# IHM.net
KiCad netlist of a schematic drawn in Altium Designer
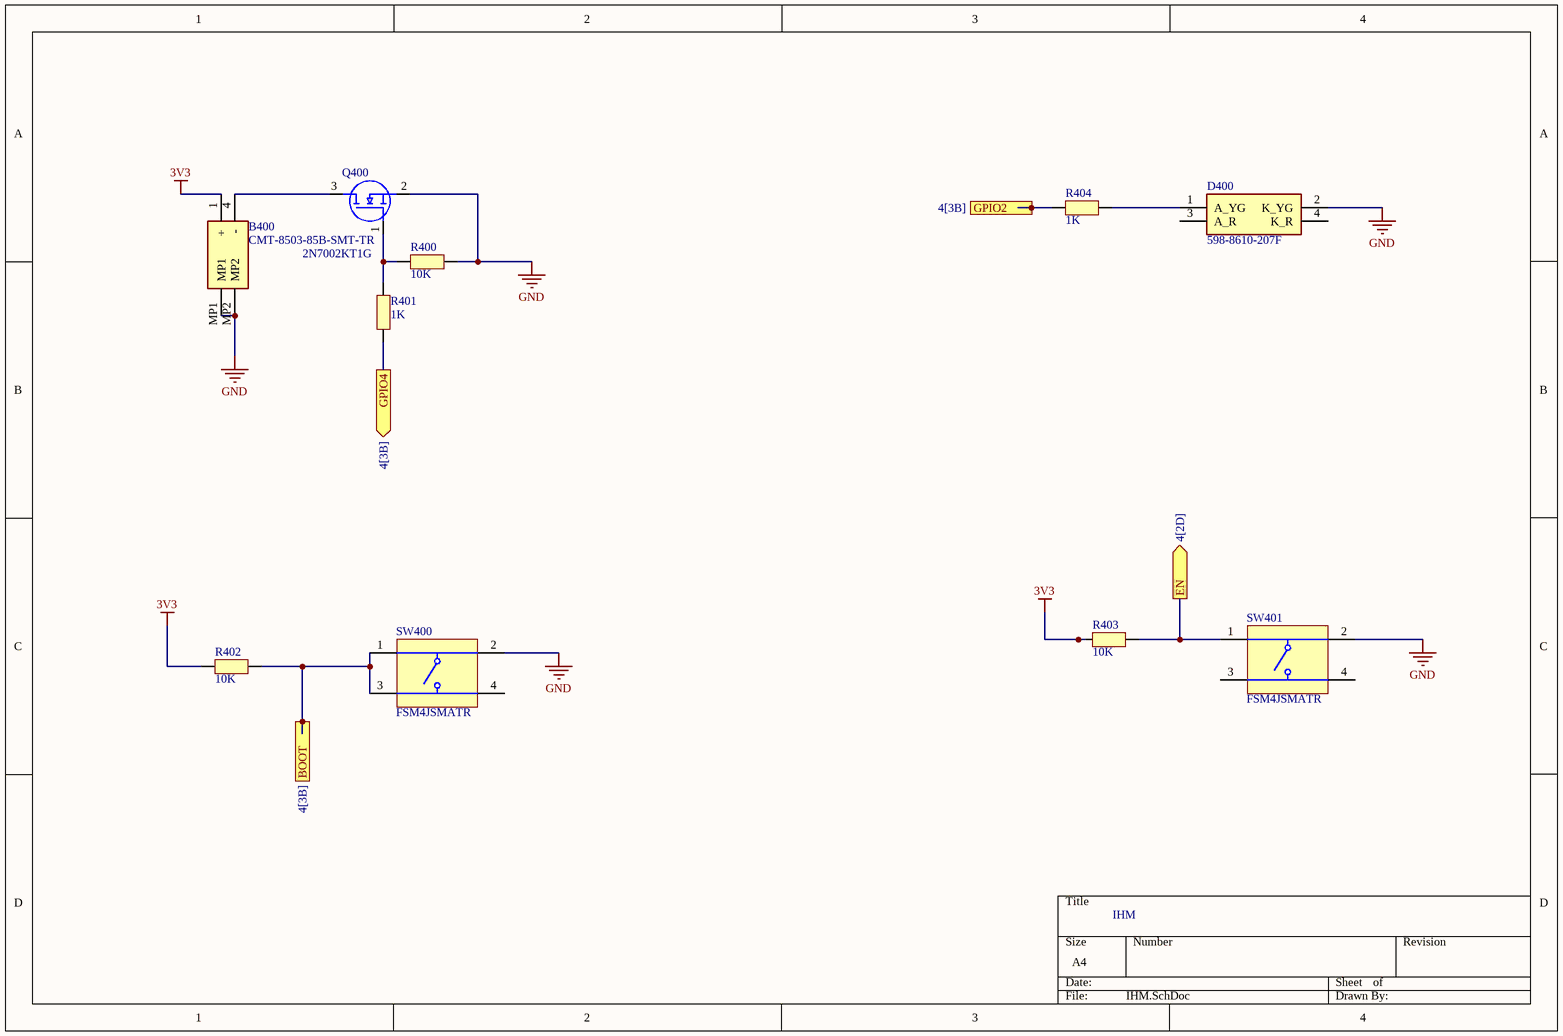
[diagram p0: IHM.SchDoc]

(export (version "E")
  (design (tool "Eeschema 10.0.6"))
  (components
    (comp (ref "B400")
      (value "CMT-8503-85B-SMT-TR")
      (footprint "CMT850385BSMTTR")
      (fields (field (name "MOUSER PART NUMBER") "490-CMT-850385BSMTTR"))
      (libsource (lib "SCHLibrary") (part "CMT-8503-85B-SMT-TR"))
    )
    (comp (ref "D400")
      (value "598-8610-207F")
      (footprint "5988610207F")
      (description "Standard LEDs - SMD Red/Green WC 80/50mcd 645/570nm")
      (fields (field (name "MOUSER PART NUMBER") "645-598-8610-207F"))
      (libsource (lib "SCHLibrary") (part "598-8610-207F"))
    )
    (comp (ref "Q400")
      (value "2N7002KT1G")
      (footprint "SOT96P237X111-3N")
      (fields (field (name "MOUSER PART NUMBER") "863-2N7002KT1G"))
      (libsource (lib "SCHLibrary") (part "2N7002KT1G"))
    )
    (comp (ref "R400")
      (value "10K")
      (footprint "RESC1005X06N")
      (libsource (lib "SCHLibrary") (part "Resistor"))
    )
    (comp (ref "R401") (value "1K") (footprint "RESC1005X06N") (libsource (lib "") (part "Resistor_2")))
    (comp (ref "R402") (value "10K") (footprint "RESC1005X06N") (libsource (lib "") (part "Resistor_1")))
    (comp (ref "R403") (value "10K") (footprint "RESC1005X06N") (libsource (lib "") (part "Resistor_1")))
    (comp (ref "R404") (value "1K") (footprint "RESC1005X06N") (libsource (lib "") (part "Resistor_1")))
    (comp (ref "SW400")
      (value "FSM4JSMATR")
      (footprint "TECO-FSM4JSMATR_V")
      (description "Micro Miniature Push Button Switch FSM JSM, 50 mA, -35 to 85 degC, 4-Pin SMD, RoHS, Tape and Reel")
      (fields (field (name "MANUFACTURER") "TE Connectivity"))
      (libsource (lib "SCHLibrary") (part "CMP-2000-07486-1"))
    )
    (comp (ref "SW401")
      (value "FSM4JSMATR")
      (footprint "TECO-FSM4JSMATR_V")
      (description "Micro Miniature Push Button Switch FSM JSM, 50 mA, -35 to 85 degC, 4-Pin SMD, RoHS, Tape and Reel")
      (fields (field (name "MANUFACTURER") "TE Connectivity"))
      (libsource (lib "SCHLibrary") (part "CMP-2000-07486-1"))
    )
  )
  (nets
    (net (code "1") (name "/BOOT") (class "Default")
      (node (ref "R402") (pin "1") (pinfunction "1_1") (pintype "passive"))
      (node (ref "SW400") (pin "1") (pinfunction "1_1") (pintype "passive"))
      (node (ref "SW400") (pin "3") (pinfunction "3_3") (pintype "passive"))
    )
    (net (code "2") (name "/EN") (class "Default")
      (node (ref "R403") (pin "1") (pinfunction "1_1") (pintype "passive"))
      (node (ref "SW401") (pin "1") (pinfunction "1_1") (pintype "passive"))
    )
    (net (code "3") (name "/GPIO2") (class "Default")
      (node (ref "R404") (pin "2") (pinfunction "2_2") (pintype "passive"))
    )
    (net (code "4") (name "/GPIO4") (class "Default")
      (node (ref "R401") (pin "1") (pinfunction "1_1") (pintype "passive"))
    )
    (net (code "5") (name "3V3") (class "Default")
      (node (ref "B400") (pin "1") (pinfunction "+_1") (pintype "passive"))
      (node (ref "R402") (pin "2") (pinfunction "2_2") (pintype "passive"))
      (node (ref "R403") (pin "2") (pinfunction "2_2") (pintype "passive"))
    )
    (net (code "6") (name "GND") (class "Default")
      (node (ref "B400") (pin "MP1") (pinfunction "MP1_MP1") (pintype "passive"))
      (node (ref "B400") (pin "MP2") (pinfunction "MP2_MP2") (pintype "passive"))
      (node (ref "D400") (pin "2") (pinfunction "K_YG_2") (pintype "passive"))
      (node (ref "Q400") (pin "2") (pinfunction "S_2") (pintype "passive"))
      (node (ref "R400") (pin "2") (pinfunction "2_2") (pintype "passive"))
      (node (ref "SW400") (pin "2") (pinfunction "2_2") (pintype "passive"))
      (node (ref "SW401") (pin "2") (pinfunction "2_2") (pintype "passive"))
    )
    (net (code "7") (name "Net-(B400--)") (class "Default")
      (node (ref "B400") (pin "4") (pinfunction "-_4") (pintype "passive"))
      (node (ref "Q400") (pin "3") (pinfunction "D_3") (pintype "passive"))
    )
    (net (code "8") (name "Net-(D400-A_YG)") (class "Default")
      (node (ref "D400") (pin "1") (pinfunction "A_YG_1") (pintype "passive"))
      (node (ref "R404") (pin "1") (pinfunction "1_1") (pintype "passive"))
    )
    (net (code "9") (name "Net-(Q400-G)") (class "Default")
      (node (ref "Q400") (pin "1") (pinfunction "G_1") (pintype "passive"))
      (node (ref "R400") (pin "1") (pinfunction "1_1") (pintype "passive"))
      (node (ref "R401") (pin "2") (pinfunction "2_2") (pintype "passive"))
    )
    (net (code "10") (name "unconnected-(D400-A_R-Pad3)") (class "Default")
      (node (ref "D400") (pin "3") (pinfunction "A_R_3") (pintype "passive"))
    )
    (net (code "11") (name "unconnected-(D400-K_R-Pad4)") (class "Default")
      (node (ref "D400") (pin "4") (pinfunction "K_R_4") (pintype "passive"))
    )
    (net (code "12") (name "unconnected-(SW400-Pad4)") (class "Default")
      (node (ref "SW400") (pin "4") (pinfunction "4_4") (pintype "passive"))
    )
    (net (code "13") (name "unconnected-(SW401-Pad3)") (class "Default")
      (node (ref "SW401") (pin "3") (pinfunction "3_3") (pintype "passive"))
    )
    (net (code "14") (name "unconnected-(SW401-Pad4)") (class "Default")
      (node (ref "SW401") (pin "4") (pinfunction "4_4") (pintype "passive"))
    )
  )
)
